# BikerBlinker.net
KiCad netlist of a schematic drawn in Altium Designer
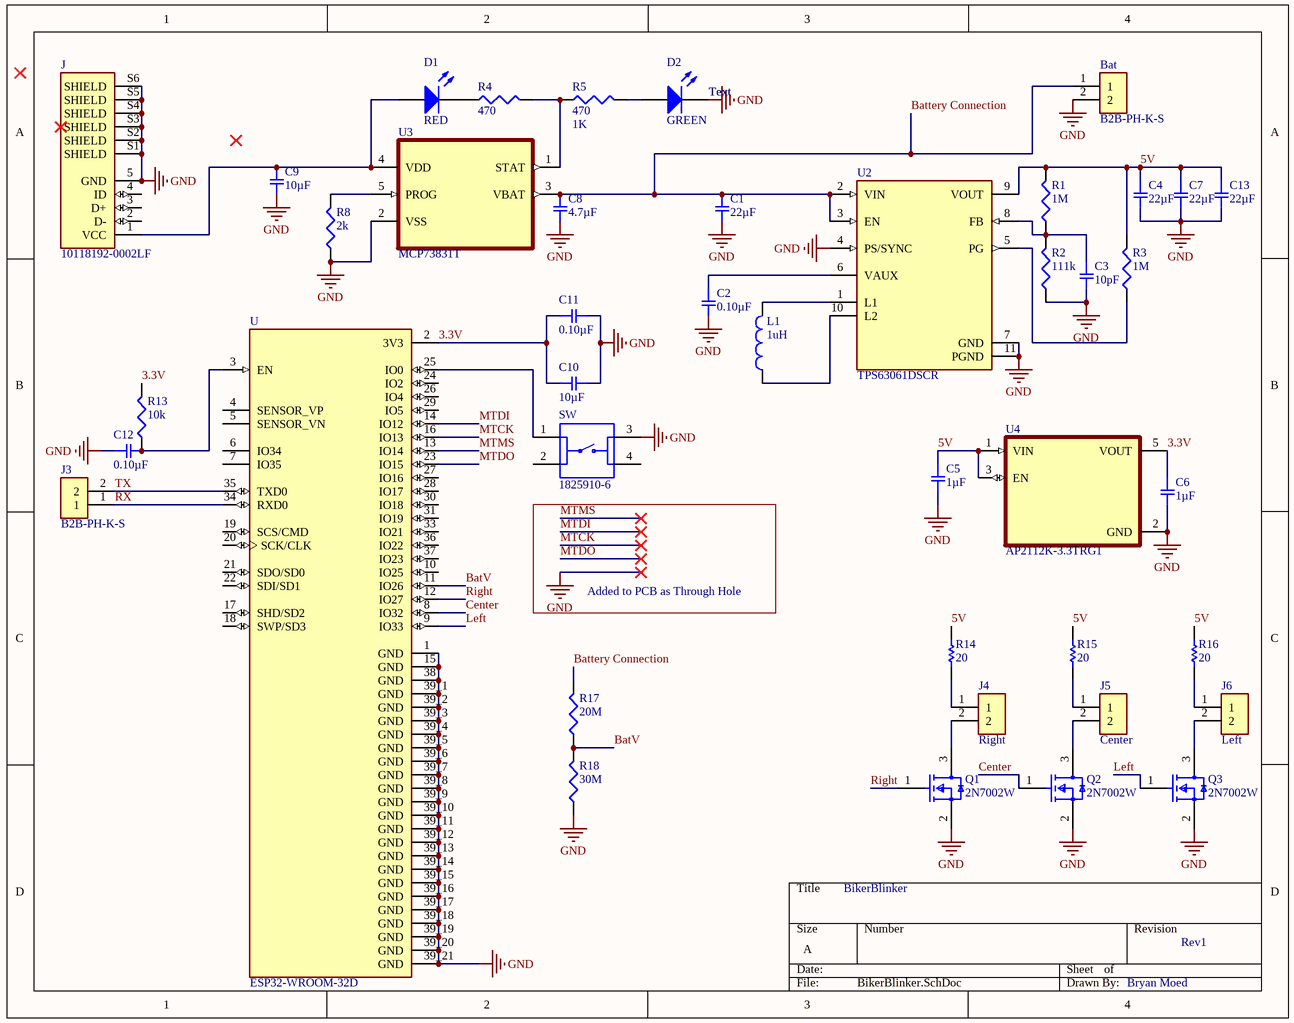
[diagram p0: BikerBlinker.SchDoc]

(export (version "E")
  (design (tool "Eeschema 10.0.6"))
  (components
    (comp (ref "Bat")
      (value "B2B-PH-K-S")
      (footprint "JST_B2B-PH-K-S(LF)(SN)")
      (description "Connector Header Through Hole 2 position 0.079 _2.00mm_")
      (fields (field (name "MF") "JST Sales") (field (name "MP") "B2B-PH-K-S_LF__SN_"))
      (libsource (lib "B2B-PH-K-S_LF__SN_") (part "B2B-PH-K-S(LF)(SN)"))
    )
    (comp (ref "C1")
      (value "22µF")
      (footprint "SMD-0603C")
      (description "CAP CER 22UF 6.3V X5R 0603")
      (fields
        (field (name "DIGI-KEY PART NUMBER") "490-13241-1-ND")
        (field (name "PART NUMBER") "GRM186R60J226ME15D")
      )
      (libsource (lib "capacitor_murata_0603") (part "GRM186R60J226ME15D"))
    )
    (comp (ref "C2")
      (value "0.10µF")
      (footprint "SMD-0603C")
      (description "CAP CER 0.1UF 16V X7R 0603")
      (fields
        (field (name "DIGI-KEY PART NUMBER") "490-5796-1-ND")
        (field (name "PART NUMBER") "GCJ188R71C104KA01D")
      )
      (libsource (lib "capacitor_murata_0603") (part "GCJ188R71C104KA01D"))
    )
    (comp (ref "C3")
      (value "10pF")
      (footprint "SMD-0603C")
      (description "CAP CER 10PF 50V NP0 0603")
      (fields
        (field (name "DIGI-KEY PART NUMBER") "490-12530-1-ND")
        (field (name "PART NUMBER") "GCM1885C1H100FA16D")
      )
      (libsource (lib "capacitor_murata_0603") (part "GCM1885C1H100FA16D"))
    )
    (comp (ref "C4")
      (value "22µF")
      (footprint "SMD-0603C")
      (description "CAP CER 22UF 6.3V X5R 0603")
      (fields
        (field (name "DIGI-KEY PART NUMBER") "490-13241-1-ND")
        (field (name "PART NUMBER") "GRM186R60J226ME15D")
      )
      (libsource (lib "capacitor_murata_0603") (part "GRM186R60J226ME15D"))
    )
    (comp (ref "C5")
      (value "1µF")
      (footprint "SMD-0603C")
      (description "CAP CER 1UF 16V X7R 0603")
      (fields
        (field (name "DIGI-KEY PART NUMBER") "490-5241-1-ND")
        (field (name "PART NUMBER") "GCM188R71C105KA64D")
      )
      (libsource (lib "capacitor_murata_0603") (part "GCM188R71C105KA64D"))
    )
    (comp (ref "C6")
      (value "1µF")
      (footprint "SMD-0603C")
      (description "CAP CER 1UF 16V X7R 0603")
      (fields
        (field (name "DIGI-KEY PART NUMBER") "490-5241-1-ND")
        (field (name "PART NUMBER") "GCM188R71C105KA64D")
      )
      (libsource (lib "capacitor_murata_0603") (part "GCM188R71C105KA64D"))
    )
    (comp (ref "C7")
      (value "22µF")
      (footprint "SMD-0603C")
      (description "CAP CER 22UF 6.3V X5R 0603")
      (fields
        (field (name "DIGI-KEY PART NUMBER") "490-13241-1-ND")
        (field (name "PART NUMBER") "GRM186R60J226ME15D")
      )
      (libsource (lib "capacitor_murata_0603") (part "GRM186R60J226ME15D"))
    )
    (comp (ref "C8")
      (value "4.7µF")
      (footprint "SMD-0603C")
      (description "CAP CER 4.7UF 6.3V X7S 0603")
      (fields
        (field (name "DIGI-KEY PART NUMBER") "490-10884-1-ND")
        (field (name "PART NUMBER") "GRJ188C70J475KE11D")
      )
      (libsource (lib "capacitor_murata_0603") (part "GRJ188C70J475KE11D"))
    )
    (comp (ref "C9")
      (value "10µF")
      (footprint "SMD-0603C")
      (description "CAP CER 10UF 6.3V X5R 0603")
      (fields
        (field (name "DIGI-KEY PART NUMBER") "490-10467-1-ND")
        (field (name "PART NUMBER") "GRM185R60J106ME15D")
      )
      (libsource (lib "capacitor_murata_0603") (part "GRM185R60J106ME15D"))
    )
    (comp (ref "C10")
      (value "10µF")
      (footprint "SMD-0603C")
      (description "CAP CER 10UF 6.3V X5R 0603")
      (fields
        (field (name "DIGI-KEY PART NUMBER") "490-10467-1-ND")
        (field (name "PART NUMBER") "GRM185R60J106ME15D")
      )
      (libsource (lib "capacitor_murata_0603") (part "GRM185R60J106ME15D"))
    )
    (comp (ref "C11")
      (value "0.10µF")
      (footprint "SMD-0603C")
      (description "CAP CER 0.1UF 16V X7R 0603")
      (fields
        (field (name "DIGI-KEY PART NUMBER") "490-5796-1-ND")
        (field (name "PART NUMBER") "GCJ188R71C104KA01D")
      )
      (libsource (lib "capacitor_murata_0603") (part "GCJ188R71C104KA01D"))
    )
    (comp (ref "C12")
      (value "0.10µF")
      (footprint "SMD-0603C")
      (description "CAP CER 0.1UF 16V X7R 0603")
      (fields
        (field (name "DIGI-KEY PART NUMBER") "490-5796-1-ND")
        (field (name "PART NUMBER") "GCJ188R71C104KA01D")
      )
      (libsource (lib "capacitor_murata_0603") (part "GCJ188R71C104KA01D"))
    )
    (comp (ref "C13")
      (value "22µF")
      (footprint "SMD-0603C")
      (description "CAP CER 22UF 6.3V X5R 0603")
      (fields
        (field (name "DIGI-KEY PART NUMBER") "490-13241-1-ND")
        (field (name "PART NUMBER") "GRM186R60J226ME15D")
      )
      (libsource (lib "capacitor_murata_0603") (part "GRM186R60J226ME15D"))
    )
    (comp (ref "D1")
      (value "RED")
      (footprint "J1-0603")
      (description "Typical RED GaAs LED")
      (fields (field (name "PUBLISHER") "Altium Limited"))
      (libsource (lib "Miscellaneous Devices") (part "LED1"))
    )
    (comp (ref "D2")
      (value "GREEN")
      (footprint "J1-0603")
      (description "Typical RED GaAs LED")
      (fields (field (name "PUBLISHER") "Altium Limited"))
      (libsource (lib "Miscellaneous Devices") (part "LED1"))
    )
    (comp (ref "J")
      (value "10118192-0002LF")
      (footprint "AMPHENOL_10118192-0002LF")
      (description "USB - micro B USB 2.0 Receptacle Connector 5 Position Surface Mount, Right Angle")
      (fields (field (name "MF") "Amphenol ICC"))
      (libsource (lib "10118192-0002LF") (part "10118192-0002LF"))
    )
    (comp (ref "J3")
      (value "B2B-PH-K-S")
      (footprint "JST_B2B-PH-K-S(LF)(SN)")
      (description "Connector Header Through Hole 2 position 0.079 _2.00mm_")
      (fields (field (name "MF") "JST Sales") (field (name "MP") "B2B-PH-K-S_LF__SN_"))
      (libsource (lib "") (part "B2B-PH-K-S(LF)(SN)_1"))
    )
    (comp (ref "J4")
      (value "Right")
      (footprint "JST_B2B-PH-K-S(LF)(SN)")
      (description "Connector Header Through Hole 2 position 0.079 _2.00mm_")
      (fields (field (name "MF") "JST Sales") (field (name "MP") "B2B-PH-K-S_LF__SN_"))
      (libsource (lib "B2B-PH-K-S_LF__SN_") (part "B2B-PH-K-S(LF)(SN)"))
    )
    (comp (ref "J5")
      (value "Center")
      (footprint "JST_B2B-PH-K-S(LF)(SN)")
      (description "Connector Header Through Hole 2 position 0.079 _2.00mm_")
      (fields (field (name "MF") "JST Sales") (field (name "MP") "B2B-PH-K-S_LF__SN_"))
      (libsource (lib "B2B-PH-K-S_LF__SN_") (part "B2B-PH-K-S(LF)(SN)"))
    )
    (comp (ref "J6")
      (value "Left")
      (footprint "JST_B2B-PH-K-S(LF)(SN)")
      (description "Connector Header Through Hole 2 position 0.079 _2.00mm_")
      (fields (field (name "MF") "JST Sales") (field (name "MP") "B2B-PH-K-S_LF__SN_"))
      (libsource (lib "B2B-PH-K-S_LF__SN_") (part "B2B-PH-K-S(LF)(SN)"))
    )
    (comp (ref "L1")
      (value "1uH")
      (footprint "0603")
      (description "Inductor")
      (fields (field (name "PUBLISHER") "Altium Limited"))
      (libsource (lib "Miscellaneous Devices") (part "Inductor"))
    )
    (comp (ref "Q1")
      (value "2N7002W")
      (footprint "FP-419AB-01-IPC_C")
      (description "MOSFET N-CH 60V 115MA SOT-323")
      (libsource (lib "Altium Content Vault") (part "a04dfd38ebfed9f67ad7f4c51a87371"))
    )
    (comp (ref "Q2")
      (value "2N7002W")
      (footprint "FP-419AB-01-IPC_C")
      (description "MOSFET N-CH 60V 115MA SOT-323")
      (libsource (lib "Altium Content Vault") (part "a04dfd38ebfed9f67ad7f4c51a87371"))
    )
    (comp (ref "Q3")
      (value "2N7002W")
      (footprint "FP-419AB-01-IPC_C")
      (description "MOSFET N-CH 60V 115MA SOT-323")
      (libsource (lib "Altium Content Vault") (part "a04dfd38ebfed9f67ad7f4c51a87371"))
    )
    (comp (ref "R1")
      (value "1M")
      (footprint "J1-0603")
      (description "Resistor")
      (fields (field (name "PUBLISHER") "Altium Limited"))
      (libsource (lib "Miscellaneous Devices") (part "Res3"))
    )
    (comp (ref "R2")
      (value "111k")
      (footprint "J1-0603")
      (description "Resistor")
      (fields (field (name "PUBLISHER") "Altium Limited"))
      (libsource (lib "Miscellaneous Devices") (part "Res3"))
    )
    (comp (ref "R3")
      (value "1M")
      (footprint "J1-0603")
      (description "Resistor")
      (fields (field (name "PUBLISHER") "Altium Limited"))
      (libsource (lib "Miscellaneous Devices") (part "Res3"))
    )
    (comp (ref "R4")
      (value "470")
      (footprint "J1-0603")
      (description "Resistor")
      (fields (field (name "PUBLISHER") "Altium Limited"))
      (libsource (lib "Miscellaneous Devices") (part "Res3"))
    )
    (comp (ref "R5")
      (value "470")
      (footprint "J1-0603")
      (description "Resistor")
      (fields (field (name "ALTIUM_VALUE") "1K") (field (name "PUBLISHER") "Altium Limited"))
      (libsource (lib "Miscellaneous Devices") (part "Res3"))
    )
    (comp (ref "R8")
      (value "2k")
      (footprint "J1-0603")
      (description "Resistor")
      (fields (field (name "PUBLISHER") "Altium Limited"))
      (libsource (lib "Miscellaneous Devices") (part "Res3"))
    )
    (comp (ref "R13")
      (value "10k")
      (footprint "J1-0603")
      (description "Resistor")
      (fields (field (name "PUBLISHER") "Altium Limited"))
      (libsource (lib "Miscellaneous Devices") (part "Res3"))
    )
    (comp (ref "R14")
      (value "20")
      (footprint "AXIAL-0.3")
      (description "Resistor")
      (fields (field (name "PUBLISHER") "Altium Limited"))
      (libsource (lib "Miscellaneous Devices") (part "Res1"))
    )
    (comp (ref "R15")
      (value "20")
      (footprint "AXIAL-0.3")
      (description "Resistor")
      (fields (field (name "PUBLISHER") "Altium Limited"))
      (libsource (lib "Miscellaneous Devices") (part "Res1"))
    )
    (comp (ref "R16")
      (value "20")
      (footprint "AXIAL-0.3")
      (description "Resistor")
      (fields (field (name "PUBLISHER") "Altium Limited"))
      (libsource (lib "Miscellaneous Devices") (part "Res1"))
    )
    (comp (ref "R17")
      (value "20M")
      (footprint "J1-0603")
      (description "Resistor")
      (fields (field (name "PUBLISHER") "Altium Limited"))
      (libsource (lib "Miscellaneous Devices") (part "Res3"))
    )
    (comp (ref "R18")
      (value "30M")
      (footprint "J1-0603")
      (description "Resistor")
      (fields (field (name "PUBLISHER") "Altium Limited"))
      (libsource (lib "Miscellaneous Devices") (part "Res3"))
    )
    (comp (ref "SW")
      (value "1825910-6")
      (footprint "SW_1825910-6-4")
      (description "Switch Push Button OFF _ON_ SPST Round Button 0.05A 24VDC Momentary Contact PC Pins Thru-Hole")
      (fields (field (name "MF") "TE Connectivity") (field (name "DIGI-KEY_PART_NUMBER") "450-1650-ND"))
      (libsource (lib "1825910-6") (part "1825910-6"))
    )
    (comp (ref "U")
      (value "ESP32-WROOM-32D")
      (footprint "MODULE_ESP32-WROOM-32D")
      (fields (field (name "MF") "Espressif Systems"))
      (libsource (lib "ESP32-WROOM-32D") (part "ESP32-WROOM-32D"))
    )
    (comp (ref "U2")
      (value "TPS63061DSCR")
      (footprint "CONV_TPS63061DSCR")
      (libsource (lib "TPS63061DSCR") (part "TPS63061DSCR"))
    )
    (comp (ref "U3")
      (value "MCP73831T")
      (footprint "SOT95P280X145-5N")
      (description "Charger IC Lithium Ion/Polymer SOT-23-5")
      (fields (field (name "MP") "MCP73831T-4ADI/OT") (field (name "MF") "Microchip"))
      (libsource (lib "MCP73831T-4ADI_OT") (part "MCP73831T-4ADI/OT"))
    )
    (comp (ref "U4")
      (value "AP2112K-3.3TRG1")
      (footprint "SOT95P285X140-5N")
      (description "Linear Voltage Regulator IC 1 Output 600mA SOT-25")
      (fields (field (name "MF") "Diodes Inc."))
      (libsource (lib "AP2112K-1.8TRG1") (part "AP2112K-1.8TRG1"))
    )
  )
  (nets
    (net (code "1") (name "/3.3V") (class "Default")
      (node (ref "C10") (pin "1") (pinfunction "1_1") (pintype "passive"))
      (node (ref "C11") (pin "1") (pinfunction "1_1") (pintype "passive"))
      (node (ref "C6") (pin "1") (pinfunction "1_1") (pintype "passive"))
      (node (ref "R13") (pin "2") (pinfunction "2_2") (pintype "passive"))
      (node (ref "U") (pin "2") (pinfunction "3V3_2") (pintype "power_in"))
      (node (ref "U4") (pin "5") (pinfunction "VOUT_5") (pintype "power_in"))
    )
    (net (code "2") (name "/5V") (class "Default")
      (node (ref "C13") (pin "1") (pinfunction "1_1") (pintype "passive"))
      (node (ref "C4") (pin "1") (pinfunction "1_1") (pintype "passive"))
      (node (ref "C5") (pin "1") (pinfunction "1_1") (pintype "passive"))
      (node (ref "C7") (pin "1") (pinfunction "1_1") (pintype "passive"))
      (node (ref "R1") (pin "2") (pinfunction "2_2") (pintype "passive"))
      (node (ref "R14") (pin "2") (pinfunction "2_2") (pintype "passive"))
      (node (ref "R15") (pin "2") (pinfunction "2_2") (pintype "passive"))
      (node (ref "R16") (pin "2") (pinfunction "2_2") (pintype "passive"))
      (node (ref "R3") (pin "2") (pinfunction "2_2") (pintype "passive"))
      (node (ref "U2") (pin "9") (pinfunction "VOUT_9") (pintype "power_in"))
      (node (ref "U4") (pin "1") (pinfunction "VIN_1") (pintype "input"))
      (node (ref "U4") (pin "3") (pinfunction "EN_3") (pintype "bidirectional"))
    )
    (net (code "3") (name "/BatV") (class "Default")
      (node (ref "R17") (pin "1") (pinfunction "1_1") (pintype "passive"))
      (node (ref "R18") (pin "2") (pinfunction "2_2") (pintype "passive"))
      (node (ref "U") (pin "11") (pinfunction "IO26_11") (pintype "bidirectional"))
    )
    (net (code "4") (name "/Battery Connection") (class "Default")
      (node (ref "Bat") (pin "1") (pinfunction "1_1") (pintype "passive"))
      (node (ref "C1") (pin "1") (pinfunction "1_1") (pintype "passive"))
      (node (ref "C8") (pin "1") (pinfunction "1_1") (pintype "passive"))
      (node (ref "R17") (pin "2") (pinfunction "2_2") (pintype "passive"))
      (node (ref "U2") (pin "2") (pinfunction "VIN_2") (pintype "input"))
      (node (ref "U2") (pin "3") (pinfunction "EN_3") (pintype "input"))
      (node (ref "U3") (pin "3") (pinfunction "VBAT_3") (pintype "output"))
    )
    (net (code "5") (name "/Center") (class "Default")
      (node (ref "Q2") (pin "1") (pinfunction "Gate_1") (pintype "passive"))
      (node (ref "U") (pin "8") (pinfunction "IO32_8") (pintype "bidirectional"))
    )
    (net (code "6") (name "/Left") (class "Default")
      (node (ref "Q3") (pin "1") (pinfunction "Gate_1") (pintype "passive"))
      (node (ref "U") (pin "9") (pinfunction "IO33_9") (pintype "bidirectional"))
    )
    (net (code "7") (name "/MTCK") (class "Default")
      (node (ref "U") (pin "16") (pinfunction "IO13_16") (pintype "bidirectional"))
    )
    (net (code "8") (name "/MTDI") (class "Default")
      (node (ref "U") (pin "14") (pinfunction "IO12_14") (pintype "bidirectional+no_connect"))
    )
    (net (code "9") (name "/MTDO") (class "Default")
      (node (ref "U") (pin "23") (pinfunction "IO15_23") (pintype "bidirectional"))
    )
    (net (code "10") (name "/MTMS") (class "Default")
      (node (ref "U") (pin "13") (pinfunction "IO14_13") (pintype "bidirectional+no_connect"))
    )
    (net (code "11") (name "/RX") (class "Default")
      (node (ref "J3") (pin "1") (pinfunction "1_1") (pintype "passive"))
      (node (ref "U") (pin "34") (pinfunction "RXD0_34") (pintype "bidirectional"))
    )
    (net (code "12") (name "/Right") (class "Default")
      (node (ref "Q1") (pin "1") (pinfunction "Gate_1") (pintype "passive"))
      (node (ref "U") (pin "12") (pinfunction "IO27_12") (pintype "bidirectional"))
    )
    (net (code "13") (name "/TX") (class "Default")
      (node (ref "J3") (pin "2") (pinfunction "2_2") (pintype "passive"))
      (node (ref "U") (pin "35") (pinfunction "TXD0_35") (pintype "bidirectional"))
    )
    (net (code "14") (name "GND") (class "Default")
      (node (ref "Bat") (pin "2") (pinfunction "2_2") (pintype "passive"))
      (node (ref "C1") (pin "2") (pinfunction "2_2") (pintype "passive"))
      (node (ref "C10") (pin "2") (pinfunction "2_2") (pintype "passive"))
      (node (ref "C11") (pin "2") (pinfunction "2_2") (pintype "passive"))
      (node (ref "C12") (pin "1") (pinfunction "1_1") (pintype "passive"))
      (node (ref "C13") (pin "2") (pinfunction "2_2") (pintype "passive"))
      (node (ref "C2") (pin "2") (pinfunction "2_2") (pintype "passive"))
      (node (ref "C3") (pin "2") (pinfunction "2_2") (pintype "passive"))
      (node (ref "C4") (pin "2") (pinfunction "2_2") (pintype "passive"))
      (node (ref "C5") (pin "2") (pinfunction "2_2") (pintype "passive"))
      (node (ref "C6") (pin "2") (pinfunction "2_2") (pintype "passive"))
      (node (ref "C7") (pin "2") (pinfunction "2_2") (pintype "passive"))
      (node (ref "C8") (pin "2") (pinfunction "2_2") (pintype "passive"))
      (node (ref "C9") (pin "2") (pinfunction "2_2") (pintype "passive"))
      (node (ref "D2") (pin "2") (pinfunction "K_2") (pintype "passive"))
      (node (ref "J") (pin "5") (pinfunction "GND_5") (pintype "power_in"))
      (node (ref "J") (pin "S1") (pinfunction "SHIELD_S1") (pintype "passive"))
      (node (ref "J") (pin "S2") (pinfunction "SHIELD_S2") (pintype "passive"))
      (node (ref "J") (pin "S3") (pinfunction "SHIELD_S3") (pintype "passive"))
      (node (ref "J") (pin "S4") (pinfunction "SHIELD_S4") (pintype "passive"))
      (node (ref "J") (pin "S5") (pinfunction "SHIELD_S5") (pintype "passive"))
      (node (ref "J") (pin "S6") (pinfunction "SHIELD_S6") (pintype "passive"))
      (node (ref "Q1") (pin "2") (pinfunction "Source_2") (pintype "passive"))
      (node (ref "Q2") (pin "2") (pinfunction "Source_2") (pintype "passive"))
      (node (ref "Q3") (pin "2") (pinfunction "Source_2") (pintype "passive"))
      (node (ref "R18") (pin "1") (pinfunction "1_1") (pintype "passive"))
      (node (ref "R2") (pin "1") (pinfunction "1_1") (pintype "passive"))
      (node (ref "R8") (pin "1") (pinfunction "1_1") (pintype "passive"))
      (node (ref "SW") (pin "3") (pinfunction "3_3") (pintype "passive"))
      (node (ref "U") (pin "1") (pinfunction "GND_1") (pintype "power_in"))
      (node (ref "U") (pin "15") (pinfunction "GND_15") (pintype "power_in"))
      (node (ref "U") (pin "38") (pinfunction "GND_38") (pintype "power_in"))
      (node (ref "U") (pin "39_1") (pinfunction "GND_39_1") (pintype "power_in"))
      (node (ref "U") (pin "39_10") (pinfunction "GND_39_10") (pintype "power_in"))
      (node (ref "U") (pin "39_11") (pinfunction "GND_39_11") (pintype "power_in"))
      (node (ref "U") (pin "39_12") (pinfunction "GND_39_12") (pintype "power_in"))
      (node (ref "U") (pin "39_13") (pinfunction "GND_39_13") (pintype "power_in"))
      (node (ref "U") (pin "39_14") (pinfunction "GND_39_14") (pintype "power_in"))
      (node (ref "U") (pin "39_15") (pinfunction "GND_39_15") (pintype "power_in"))
      (node (ref "U") (pin "39_16") (pinfunction "GND_39_16") (pintype "power_in"))
      (node (ref "U") (pin "39_17") (pinfunction "GND_39_17") (pintype "power_in"))
      (node (ref "U") (pin "39_18") (pinfunction "GND_39_18") (pintype "power_in"))
      (node (ref "U") (pin "39_19") (pinfunction "GND_39_19") (pintype "power_in"))
      (node (ref "U") (pin "39_2") (pinfunction "GND_39_2") (pintype "power_in"))
      (node (ref "U") (pin "39_20") (pinfunction "GND_39_20") (pintype "power_in"))
      (node (ref "U") (pin "39_21") (pinfunction "GND_39_21") (pintype "power_in"))
      (node (ref "U") (pin "39_3") (pinfunction "GND_39_3") (pintype "power_in"))
      (node (ref "U") (pin "39_4") (pinfunction "GND_39_4") (pintype "power_in"))
      (node (ref "U") (pin "39_5") (pinfunction "GND_39_5") (pintype "power_in"))
      (node (ref "U") (pin "39_6") (pinfunction "GND_39_6") (pintype "power_in"))
      (node (ref "U") (pin "39_7") (pinfunction "GND_39_7") (pintype "power_in"))
      (node (ref "U") (pin "39_8") (pinfunction "GND_39_8") (pintype "power_in"))
      (node (ref "U") (pin "39_9") (pinfunction "GND_39_9") (pintype "power_in"))
      (node (ref "U2") (pin "11") (pinfunction "PGND_11") (pintype "power_in"))
      (node (ref "U2") (pin "4") (pinfunction "PS/SYNC_4") (pintype "input"))
      (node (ref "U2") (pin "7") (pinfunction "GND_7") (pintype "power_in"))
      (node (ref "U3") (pin "2") (pinfunction "VSS_2") (pintype "power_in"))
      (node (ref "U4") (pin "2") (pinfunction "GND_2") (pintype "power_in"))
    )
    (net (code "15") (name "Net-(D1-A)") (class "Default")
      (node (ref "C9") (pin "1") (pinfunction "1_1") (pintype "passive"))
      (node (ref "D1") (pin "1") (pinfunction "A_1") (pintype "passive"))
      (node (ref "J") (pin "1") (pinfunction "VCC_1") (pintype "power_in"))
      (node (ref "U3") (pin "4") (pinfunction "VDD_4") (pintype "power_in"))
    )
    (net (code "16") (name "Net-(D1-K)") (class "Default")
      (node (ref "D1") (pin "2") (pinfunction "K_2") (pintype "passive"))
      (node (ref "R4") (pin "1") (pinfunction "1_1") (pintype "passive"))
    )
    (net (code "17") (name "Net-(D2-A)") (class "Default")
      (node (ref "D2") (pin "1") (pinfunction "A_1") (pintype "passive"))
      (node (ref "R5") (pin "2") (pinfunction "2_2") (pintype "passive"))
    )
    (net (code "18") (name "Net-(J4-Pad1)") (class "Default")
      (node (ref "J4") (pin "1") (pinfunction "1_1") (pintype "passive"))
      (node (ref "R14") (pin "1") (pinfunction "1_1") (pintype "passive"))
    )
    (net (code "19") (name "Net-(J5-Pad1)") (class "Default")
      (node (ref "J5") (pin "1") (pinfunction "1_1") (pintype "passive"))
      (node (ref "R15") (pin "1") (pinfunction "1_1") (pintype "passive"))
    )
    (net (code "20") (name "Net-(J6-Pad1)") (class "Default")
      (node (ref "J6") (pin "1") (pinfunction "1_1") (pintype "passive"))
      (node (ref "R16") (pin "1") (pinfunction "1_1") (pintype "passive"))
    )
    (net (code "21") (name "Net-(Q1-Drain)") (class "Default")
      (node (ref "J4") (pin "2") (pinfunction "2_2") (pintype "passive"))
      (node (ref "Q1") (pin "3") (pinfunction "Drain_3") (pintype "passive"))
    )
    (net (code "22") (name "Net-(Q2-Drain)") (class "Default")
      (node (ref "J5") (pin "2") (pinfunction "2_2") (pintype "passive"))
      (node (ref "Q2") (pin "3") (pinfunction "Drain_3") (pintype "passive"))
    )
    (net (code "23") (name "Net-(Q3-Drain)") (class "Default")
      (node (ref "J6") (pin "2") (pinfunction "2_2") (pintype "passive"))
      (node (ref "Q3") (pin "3") (pinfunction "Drain_3") (pintype "passive"))
    )
    (net (code "24") (name "Net-(U-EN)") (class "Default")
      (node (ref "C12") (pin "2") (pinfunction "2_2") (pintype "passive"))
      (node (ref "R13") (pin "1") (pinfunction "1_1") (pintype "passive"))
      (node (ref "U") (pin "3") (pinfunction "EN_3") (pintype "input"))
    )
    (net (code "25") (name "Net-(U-IO0)") (class "Default")
      (node (ref "SW") (pin "1") (pinfunction "1_1") (pintype "passive"))
      (node (ref "U") (pin "25") (pinfunction "IO0_25") (pintype "bidirectional"))
    )
    (net (code "26") (name "Net-(U2-FB)") (class "Default")
      (node (ref "C3") (pin "1") (pinfunction "1_1") (pintype "passive"))
      (node (ref "R1") (pin "1") (pinfunction "1_1") (pintype "passive"))
      (node (ref "R2") (pin "2") (pinfunction "2_2") (pintype "passive"))
      (node (ref "U2") (pin "8") (pinfunction "FB_8") (pintype "input"))
    )
    (net (code "27") (name "Net-(U2-L1)") (class "Default")
      (node (ref "L1") (pin "2") (pinfunction "2_2") (pintype "passive"))
      (node (ref "U2") (pin "1") (pinfunction "L1_1") (pintype "passive"))
    )
    (net (code "28") (name "Net-(U2-L2)") (class "Default")
      (node (ref "L1") (pin "1") (pinfunction "1_1") (pintype "passive"))
      (node (ref "U2") (pin "10") (pinfunction "L2_10") (pintype "passive"))
    )
    (net (code "29") (name "Net-(U2-PG)") (class "Default")
      (node (ref "R3") (pin "1") (pinfunction "1_1") (pintype "passive"))
      (node (ref "U2") (pin "5") (pinfunction "PG_5") (pintype "output"))
    )
    (net (code "30") (name "Net-(U2-VAUX)") (class "Default")
      (node (ref "C2") (pin "1") (pinfunction "1_1") (pintype "passive"))
      (node (ref "U2") (pin "6") (pinfunction "VAUX_6") (pintype "passive"))
    )
    (net (code "31") (name "Net-(U3-PROG)") (class "Default")
      (node (ref "R8") (pin "2") (pinfunction "2_2") (pintype "passive"))
      (node (ref "U3") (pin "5") (pinfunction "PROG_5") (pintype "input"))
    )
    (net (code "32") (name "Net-(U3-STAT)") (class "Default")
      (node (ref "R4") (pin "2") (pinfunction "2_2") (pintype "passive"))
      (node (ref "R5") (pin "1") (pinfunction "1_1") (pintype "passive"))
      (node (ref "U3") (pin "1") (pinfunction "STAT_1") (pintype "output"))
    )
    (net (code "33") (name "unconnected-(J-D+-Pad3)") (class "Default")
      (node (ref "J") (pin "3") (pinfunction "D+_3") (pintype "bidirectional"))
    )
    (net (code "34") (name "unconnected-(J-D--Pad2)") (class "Default")
      (node (ref "J") (pin "2") (pinfunction "D-_2") (pintype "bidirectional"))
    )
    (net (code "35") (name "unconnected-(J-ID-Pad4)") (class "Default")
      (node (ref "J") (pin "4") (pinfunction "ID_4") (pintype "bidirectional"))
    )
    (net (code "36") (name "unconnected-(SW-Pad2)") (class "Default")
      (node (ref "SW") (pin "2") (pinfunction "2_2") (pintype "passive"))
    )
    (net (code "37") (name "unconnected-(SW-Pad4)") (class "Default")
      (node (ref "SW") (pin "4") (pinfunction "4_4") (pintype "passive"))
    )
    (net (code "38") (name "unconnected-(U-IO2-Pad24)") (class "Default")
      (node (ref "U") (pin "24") (pinfunction "IO2_24") (pintype "bidirectional"))
    )
    (net (code "39") (name "unconnected-(U-IO4-Pad26)") (class "Default")
      (node (ref "U") (pin "26") (pinfunction "IO4_26") (pintype "bidirectional"))
    )
    (net (code "40") (name "unconnected-(U-IO5-Pad29)") (class "Default")
      (node (ref "U") (pin "29") (pinfunction "IO5_29") (pintype "bidirectional"))
    )
    (net (code "41") (name "unconnected-(U-IO16-Pad27)") (class "Default")
      (node (ref "U") (pin "27") (pinfunction "IO16_27") (pintype "bidirectional"))
    )
    (net (code "42") (name "unconnected-(U-IO17-Pad28)") (class "Default")
      (node (ref "U") (pin "28") (pinfunction "IO17_28") (pintype "bidirectional"))
    )
    (net (code "43") (name "unconnected-(U-IO18-Pad30)") (class "Default")
      (node (ref "U") (pin "30") (pinfunction "IO18_30") (pintype "bidirectional"))
    )
    (net (code "44") (name "unconnected-(U-IO19-Pad31)") (class "Default")
      (node (ref "U") (pin "31") (pinfunction "IO19_31") (pintype "bidirectional"))
    )
    (net (code "45") (name "unconnected-(U-IO21-Pad33)") (class "Default")
      (node (ref "U") (pin "33") (pinfunction "IO21_33") (pintype "bidirectional"))
    )
    (net (code "46") (name "unconnected-(U-IO22-Pad36)") (class "Default")
      (node (ref "U") (pin "36") (pinfunction "IO22_36") (pintype "bidirectional"))
    )
    (net (code "47") (name "unconnected-(U-IO23-Pad37)") (class "Default")
      (node (ref "U") (pin "37") (pinfunction "IO23_37") (pintype "bidirectional"))
    )
    (net (code "48") (name "unconnected-(U-IO25-Pad10)") (class "Default")
      (node (ref "U") (pin "10") (pinfunction "IO25_10") (pintype "bidirectional"))
    )
    (net (code "49") (name "unconnected-(U-IO34-Pad6)") (class "Default")
      (node (ref "U") (pin "6") (pinfunction "IO34_6") (pintype "passive"))
    )
    (net (code "50") (name "unconnected-(U-IO35-Pad7)") (class "Default")
      (node (ref "U") (pin "7") (pinfunction "IO35_7") (pintype "passive"))
    )
    (net (code "51") (name "unconnected-(U-SCK{slash}CLK-Pad20)") (class "Default")
      (node (ref "U") (pin "20") (pinfunction "SCK/CLK_20") (pintype "bidirectional"))
    )
    (net (code "52") (name "unconnected-(U-SCS{slash}CMD-Pad19)") (class "Default")
      (node (ref "U") (pin "19") (pinfunction "SCS/CMD_19") (pintype "bidirectional"))
    )
    (net (code "53") (name "unconnected-(U-SDI{slash}SD1-Pad22)") (class "Default")
      (node (ref "U") (pin "22") (pinfunction "SDI/SD1_22") (pintype "bidirectional"))
    )
    (net (code "54") (name "unconnected-(U-SDO{slash}SD0-Pad21)") (class "Default")
      (node (ref "U") (pin "21") (pinfunction "SDO/SD0_21") (pintype "bidirectional"))
    )
    (net (code "55") (name "unconnected-(U-SENSOR_VN-Pad5)") (class "Default")
      (node (ref "U") (pin "5") (pinfunction "SENSOR_VN_5") (pintype "passive"))
    )
    (net (code "56") (name "unconnected-(U-SENSOR_VP-Pad4)") (class "Default")
      (node (ref "U") (pin "4") (pinfunction "SENSOR_VP_4") (pintype "passive"))
    )
    (net (code "57") (name "unconnected-(U-SHD{slash}SD2-Pad17)") (class "Default")
      (node (ref "U") (pin "17") (pinfunction "SHD/SD2_17") (pintype "bidirectional"))
    )
    (net (code "58") (name "unconnected-(U-SWP{slash}SD3-Pad18)") (class "Default")
      (node (ref "U") (pin "18") (pinfunction "SWP/SD3_18") (pintype "bidirectional"))
    )
    (net (code "59") (name "unconnected-(U4-NC-Pad4)") (class "Default")
      (node (ref "U4") (pin "4") (pinfunction "NC_4") (pintype "bidirectional"))
    )
  )
)
